# FPGA_Power.net
KiCad netlist of a schematic drawn in Altium Designer
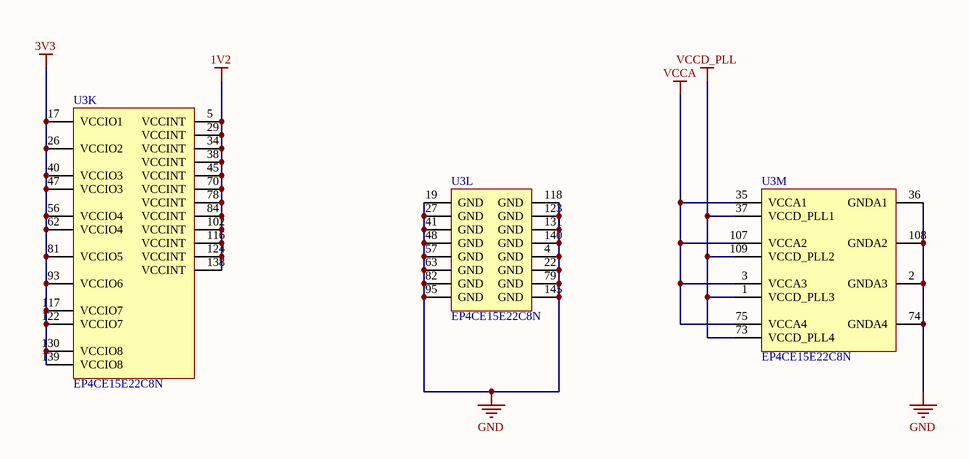
[diagram p0: FPGA_Power.SchDoc]

(export (version "E")
  (design (tool "Eeschema 10.0.6"))
  (components
    (comp (ref "U3")
      (value "EP4CE15E22C8N")
      (footprint "EQFP144_A-165_D2-67_N")
      (fields (field (name "MANUFACTURER") "Altera"))
      (libsource (lib "Altera Cyclone IV E") (part "EP4CE15E22C8N"))
    )
  )
  (nets
    (net (code "1") (name "1V2") (class "Default")
      (node (ref "U3") (pin "102") (pinfunction "VCCINT_102") (pintype "power_in"))
      (node (ref "U3") (pin "116") (pinfunction "VCCINT_116") (pintype "power_in"))
      (node (ref "U3") (pin "124") (pinfunction "VCCINT_124") (pintype "power_in"))
      (node (ref "U3") (pin "138") (pinfunction "VCCINT_138") (pintype "power_in"))
      (node (ref "U3") (pin "29") (pinfunction "VCCINT_29") (pintype "power_in"))
      (node (ref "U3") (pin "34") (pinfunction "VCCINT_34") (pintype "power_in"))
      (node (ref "U3") (pin "38") (pinfunction "VCCINT_38") (pintype "power_in"))
      (node (ref "U3") (pin "45") (pinfunction "VCCINT_45") (pintype "power_in"))
      (node (ref "U3") (pin "5") (pinfunction "VCCINT_5") (pintype "power_in"))
      (node (ref "U3") (pin "70") (pinfunction "VCCINT_70") (pintype "power_in"))
      (node (ref "U3") (pin "78") (pinfunction "VCCINT_78") (pintype "power_in"))
      (node (ref "U3") (pin "84") (pinfunction "VCCINT_84") (pintype "power_in"))
    )
    (net (code "2") (name "3V3") (class "Default")
      (node (ref "U3") (pin "117") (pinfunction "VCCIO7_117") (pintype "power_in"))
      (node (ref "U3") (pin "122") (pinfunction "VCCIO7_122") (pintype "power_in"))
      (node (ref "U3") (pin "130") (pinfunction "VCCIO8_130") (pintype "power_in"))
      (node (ref "U3") (pin "139") (pinfunction "VCCIO8_139") (pintype "power_in"))
      (node (ref "U3") (pin "17") (pinfunction "VCCIO1_17") (pintype "power_in"))
      (node (ref "U3") (pin "26") (pinfunction "VCCIO2_26") (pintype "power_in"))
      (node (ref "U3") (pin "40") (pinfunction "VCCIO3_40") (pintype "power_in"))
      (node (ref "U3") (pin "47") (pinfunction "VCCIO3_47") (pintype "power_in"))
      (node (ref "U3") (pin "56") (pinfunction "VCCIO4_56") (pintype "power_in"))
      (node (ref "U3") (pin "62") (pinfunction "VCCIO4_62") (pintype "power_in"))
      (node (ref "U3") (pin "81") (pinfunction "VCCIO5_81") (pintype "power_in"))
      (node (ref "U3") (pin "93") (pinfunction "VCCIO6_93") (pintype "power_in"))
    )
    (net (code "3") (name "GND") (class "Default")
      (node (ref "U3") (pin "108") (pinfunction "GNDA2_108") (pintype "power_in"))
      (node (ref "U3") (pin "118") (pinfunction "GND_118") (pintype "power_in"))
      (node (ref "U3") (pin "123") (pinfunction "GND_123") (pintype "power_in"))
      (node (ref "U3") (pin "131") (pinfunction "GND_131") (pintype "power_in"))
      (node (ref "U3") (pin "140") (pinfunction "GND_140") (pintype "power_in"))
      (node (ref "U3") (pin "145") (pinfunction "GND_145") (pintype "power_in"))
      (node (ref "U3") (pin "19") (pinfunction "GND_19") (pintype "power_in"))
      (node (ref "U3") (pin "2") (pinfunction "GNDA3_2") (pintype "power_in"))
      (node (ref "U3") (pin "22") (pinfunction "GND_22") (pintype "power_in"))
      (node (ref "U3") (pin "27") (pinfunction "GND_27") (pintype "power_in"))
      (node (ref "U3") (pin "36") (pinfunction "GNDA1_36") (pintype "power_in"))
      (node (ref "U3") (pin "4") (pinfunction "GND_4") (pintype "power_in"))
      (node (ref "U3") (pin "41") (pinfunction "GND_41") (pintype "power_in"))
      (node (ref "U3") (pin "48") (pinfunction "GND_48") (pintype "power_in"))
      (node (ref "U3") (pin "57") (pinfunction "GND_57") (pintype "power_in"))
      (node (ref "U3") (pin "63") (pinfunction "GND_63") (pintype "power_in"))
      (node (ref "U3") (pin "74") (pinfunction "GNDA4_74") (pintype "power_in"))
      (node (ref "U3") (pin "79") (pinfunction "GND_79") (pintype "power_in"))
      (node (ref "U3") (pin "82") (pinfunction "GND_82") (pintype "power_in"))
      (node (ref "U3") (pin "95") (pinfunction "GND_95") (pintype "power_in"))
    )
    (net (code "4") (name "VCCA") (class "Default")
      (node (ref "U3") (pin "107") (pinfunction "VCCA2_107") (pintype "power_in"))
      (node (ref "U3") (pin "3") (pinfunction "VCCA3_3") (pintype "power_in"))
      (node (ref "U3") (pin "35") (pinfunction "VCCA1_35") (pintype "power_in"))
      (node (ref "U3") (pin "75") (pinfunction "VCCA4_75") (pintype "power_in"))
    )
    (net (code "5") (name "VCCD_PLL") (class "Default")
      (node (ref "U3") (pin "1") (pinfunction "VCCD_PLL3_1") (pintype "power_in"))
      (node (ref "U3") (pin "109") (pinfunction "VCCD_PLL2_109") (pintype "power_in"))
      (node (ref "U3") (pin "37") (pinfunction "VCCD_PLL1_37") (pintype "power_in"))
      (node (ref "U3") (pin "73") (pinfunction "VCCD_PLL4_73") (pintype "power_in"))
    )
  )
)
